# ENV1.net
KiCad netlist of a schematic drawn in EAGLE
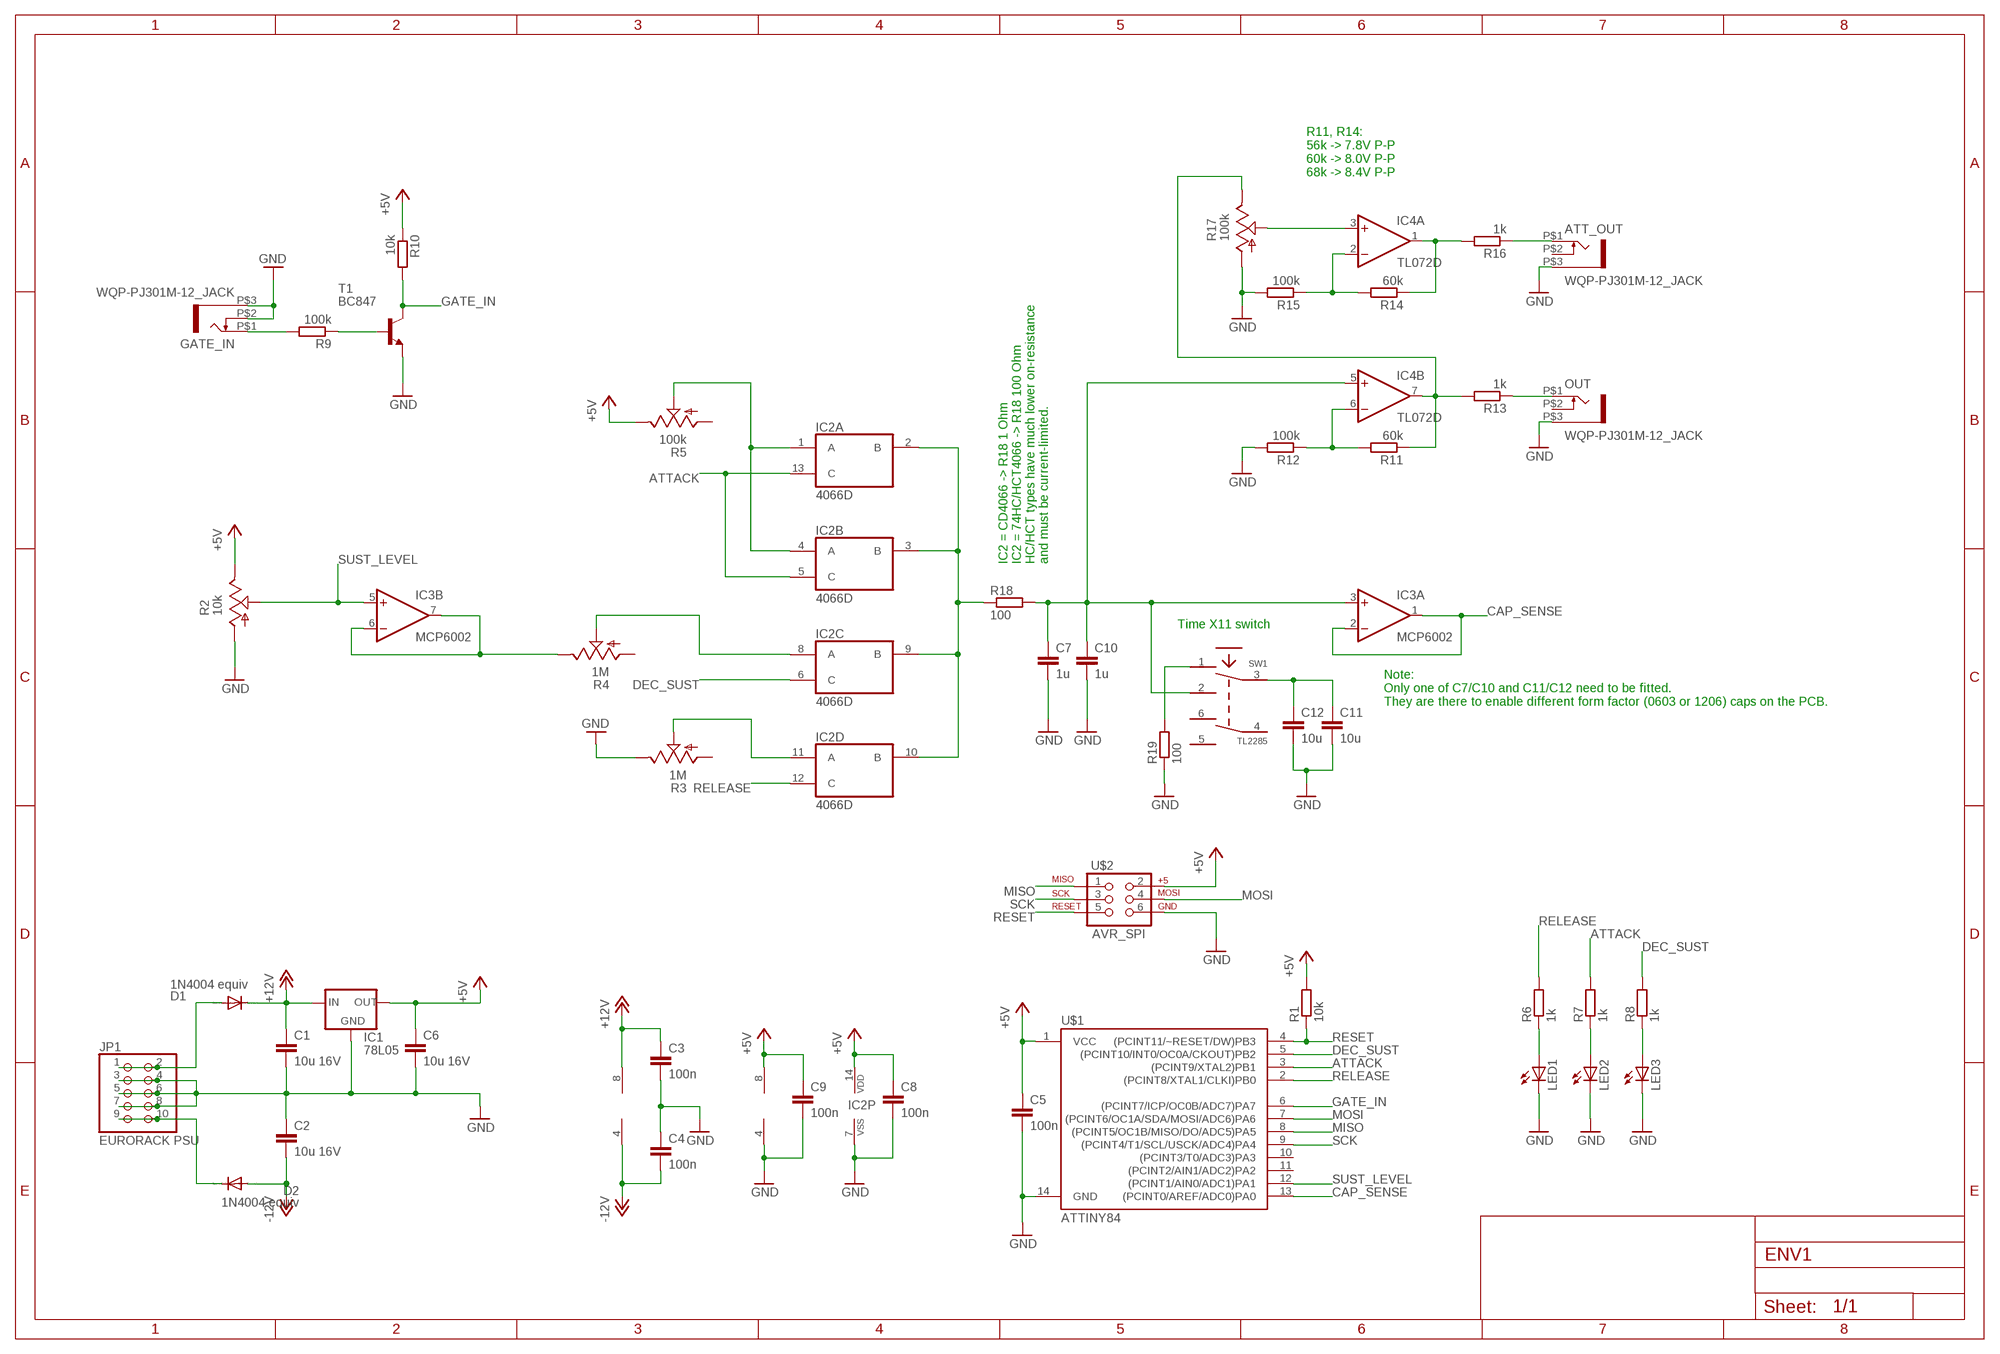
[diagram p0: schematic, sheet 1]

(export (version "E")
  (design (tool "Eeschema 10.0.6"))
  (components
    (comp (ref "ATT_OUT")
      (value "WQP-PJ301M-12_JACK")
      (footprint "eagle-import:WQP-PJ301M-12_JACK")
      (libsource (lib "eagle-import") (part "WQP-PJ301M-12_JACK"))
    )
    (comp (ref "C1")
      (value "10u 16V")
      (footprint "eagle-import:C1206K")
      (libsource (lib "eagle-import") (part "C-EUC1206K"))
    )
    (comp (ref "C2")
      (value "10u 16V")
      (footprint "eagle-import:C1206K")
      (libsource (lib "eagle-import") (part "C-EUC1206K"))
    )
    (comp (ref "C3")
      (value "100n")
      (footprint "eagle-import:C0603K")
      (libsource (lib "eagle-import") (part "C-EUC0603K"))
    )
    (comp (ref "C4")
      (value "100n")
      (footprint "eagle-import:C0603K")
      (libsource (lib "eagle-import") (part "C-EUC0603K"))
    )
    (comp (ref "C5")
      (value "100n")
      (footprint "eagle-import:C0603K")
      (libsource (lib "eagle-import") (part "C-EUC0603K"))
    )
    (comp (ref "C6")
      (value "10u 16V")
      (footprint "eagle-import:C1206K")
      (libsource (lib "eagle-import") (part "C-EUC1206K"))
    )
    (comp (ref "C7")
      (value "1u")
      (footprint "eagle-import:C0603K")
      (libsource (lib "eagle-import") (part "C-EUC0603K"))
    )
    (comp (ref "C8")
      (value "100n")
      (footprint "eagle-import:C0603K")
      (libsource (lib "eagle-import") (part "C-EUC0603K"))
    )
    (comp (ref "C9")
      (value "100n")
      (footprint "eagle-import:C0603K")
      (libsource (lib "eagle-import") (part "C-EUC0603K"))
    )
    (comp (ref "C10")
      (value "1u")
      (footprint "eagle-import:C1206K")
      (libsource (lib "eagle-import") (part "C-EUC1206K"))
    )
    (comp (ref "C11")
      (value "10u")
      (footprint "eagle-import:C1206K")
      (libsource (lib "eagle-import") (part "C-EUC1206K"))
    )
    (comp (ref "C12")
      (value "10u")
      (footprint "eagle-import:C0603K")
      (libsource (lib "eagle-import") (part "C-EUC0603K"))
    )
    (comp (ref "D1")
      (value "1N4004 equiv")
      (footprint "eagle-import:DO214AA")
      (libsource (lib "eagle-import") (part "DIODE-DO214AA"))
    )
    (comp (ref "D2")
      (value "1N4004 equiv")
      (footprint "eagle-import:DO214AA")
      (libsource (lib "eagle-import") (part "DIODE-DO214AA"))
    )
    (comp (ref "GATE_IN")
      (value "WQP-PJ301M-12_JACK")
      (footprint "eagle-import:WQP-PJ301M-12_JACK")
      (libsource (lib "eagle-import") (part "WQP-PJ301M-12_JACK"))
    )
    (comp (ref "IC1")
      (value "78L05")
      (footprint "eagle-import:SOT89R")
      (libsource (lib "eagle-import") (part "78LXXSMD"))
    )
    (comp (ref "IC2")
      (value "4066D")
      (footprint "eagle-import:SO14")
      (libsource (lib "eagle-import") (part "4066D"))
    )
    (comp (ref "IC3")
      (value "MCP6002")
      (footprint "eagle-import:SO08")
      (libsource (lib "eagle-import") (part "TL072D"))
    )
    (comp (ref "IC4")
      (value "TL072D")
      (footprint "eagle-import:SO08")
      (libsource (lib "eagle-import") (part "TL072D"))
    )
    (comp (ref "JP1")
      (value "EURORACK PSU")
      (footprint "eagle-import:2X05")
      (libsource (lib "eagle-import") (part "PINHD-2X5"))
    )
    (comp (ref "LED1")
      (value "LED3MM")
      (footprint "eagle-import:LED3MM")
      (libsource (lib "eagle-import") (part "LED3MM"))
    )
    (comp (ref "LED2")
      (value "LED3MM")
      (footprint "eagle-import:LED3MM")
      (libsource (lib "eagle-import") (part "LED3MM"))
    )
    (comp (ref "LED3")
      (value "LED3MM")
      (footprint "eagle-import:LED3MM")
      (libsource (lib "eagle-import") (part "LED3MM"))
    )
    (comp (ref "OUT")
      (value "WQP-PJ301M-12_JACK")
      (footprint "eagle-import:WQP-PJ301M-12_JACK")
      (libsource (lib "eagle-import") (part "WQP-PJ301M-12_JACK"))
    )
    (comp (ref "R1")
      (value "10k")
      (footprint "eagle-import:R0603")
      (libsource (lib "eagle-import") (part "R-EU_R0603"))
    )
    (comp (ref "R2")
      (value "10k")
      (footprint "eagle-import:ALPS_POT_VERTICAL")
      (libsource (lib "eagle-import") (part "POT_USVERTICAL"))
    )
    (comp (ref "R3")
      (value "1M")
      (footprint "eagle-import:ALPS_POT_VERTICAL")
      (libsource (lib "eagle-import") (part "POT_USVERTICAL"))
    )
    (comp (ref "R4")
      (value "1M")
      (footprint "eagle-import:ALPS_POT_VERTICAL")
      (libsource (lib "eagle-import") (part "POT_USVERTICAL"))
    )
    (comp (ref "R5")
      (value "100k")
      (footprint "eagle-import:ALPS_POT_VERTICAL")
      (libsource (lib "eagle-import") (part "POT_USVERTICAL"))
    )
    (comp (ref "R6")
      (value "1k")
      (footprint "eagle-import:R0603")
      (libsource (lib "eagle-import") (part "R-EU_R0603"))
    )
    (comp (ref "R7")
      (value "1k")
      (footprint "eagle-import:R0603")
      (libsource (lib "eagle-import") (part "R-EU_R0603"))
    )
    (comp (ref "R8")
      (value "1k")
      (footprint "eagle-import:R0603")
      (libsource (lib "eagle-import") (part "R-EU_R0603"))
    )
    (comp (ref "R9")
      (value "100k")
      (footprint "eagle-import:R0603")
      (libsource (lib "eagle-import") (part "R-EU_R0603"))
    )
    (comp (ref "R10")
      (value "10k")
      (footprint "eagle-import:R0603")
      (libsource (lib "eagle-import") (part "R-EU_R0603"))
    )
    (comp (ref "R11")
      (value "60k")
      (footprint "eagle-import:R0603")
      (libsource (lib "eagle-import") (part "R-EU_R0603"))
    )
    (comp (ref "R12")
      (value "100k")
      (footprint "eagle-import:R0603")
      (libsource (lib "eagle-import") (part "R-EU_R0603"))
    )
    (comp (ref "R13")
      (value "1k")
      (footprint "eagle-import:R0603")
      (libsource (lib "eagle-import") (part "R-EU_R0603"))
    )
    (comp (ref "R14")
      (value "60k")
      (footprint "eagle-import:R0603")
      (libsource (lib "eagle-import") (part "R-EU_R0603"))
    )
    (comp (ref "R15")
      (value "100k")
      (footprint "eagle-import:R0603")
      (libsource (lib "eagle-import") (part "R-EU_R0603"))
    )
    (comp (ref "R16")
      (value "1k")
      (footprint "eagle-import:R0603")
      (libsource (lib "eagle-import") (part "R-EU_R0603"))
    )
    (comp (ref "R17")
      (value "100k")
      (footprint "eagle-import:ALPS_POT_VERTICAL")
      (libsource (lib "eagle-import") (part "POT_USVERTICAL"))
    )
    (comp (ref "R18")
      (value "100")
      (footprint "eagle-import:R1206")
      (libsource (lib "eagle-import") (part "R-EU_R1206"))
    )
    (comp (ref "R19")
      (value "100")
      (footprint "eagle-import:R1206")
      (libsource (lib "eagle-import") (part "R-EU_R1206"))
    )
    (comp (ref "SW1")
      (value "TL2285")
      (footprint "eagle-import:TL2285_PCB")
      (libsource (lib "eagle-import") (part "TL2285"))
    )
    (comp (ref "T1")
      (value "BC847")
      (footprint "eagle-import:SOT23")
      (libsource (lib "eagle-import") (part "BC847"))
    )
    (comp (ref "U$1")
      (value "ATTINY84")
      (footprint "eagle-import:SO14")
      (libsource (lib "eagle-import") (part "ATTINY84"))
    )
    (comp (ref "U$2")
      (value "AVR_SPI")
      (footprint "eagle-import:2X3")
      (libsource (lib "eagle-import") (part "AVR_SPI_PRG_6PTH"))
    )
  )
  (nets
    (net (code "1") (name "+5V") (class "Default")
      (node (ref "C5") (pin "1") (pinfunction "1_1") (pintype "passive"))
      (node (ref "C6") (pin "1") (pinfunction "1_1") (pintype "passive"))
      (node (ref "C8") (pin "1") (pinfunction "1_1") (pintype "passive"))
      (node (ref "C9") (pin "1") (pinfunction "1_1") (pintype "passive"))
      (node (ref "IC1") (pin "PAD1") (pinfunction "OUT_PAD1") (pintype "passive"))
      (node (ref "IC2") (pin "14") (pinfunction "VDD_14") (pintype "power_in"))
      (node (ref "IC3") (pin "8") (pinfunction "V+_8") (pintype "power_in"))
      (node (ref "R1") (pin "2") (pinfunction "2_2") (pintype "passive"))
      (node (ref "R10") (pin "1") (pinfunction "1_1") (pintype "passive"))
      (node (ref "R2") (pin "P$1") (pinfunction "E_P$1") (pintype "passive"))
      (node (ref "R5") (pin "P$1") (pinfunction "E_P$1") (pintype "passive"))
      (node (ref "U$1") (pin "1") (pinfunction "VCC_1") (pintype "bidirectional"))
      (node (ref "U$2") (pin "2") (pinfunction "2_2") (pintype "passive"))
    )
    (net (code "2") (name "+12V") (class "Default")
      (node (ref "C1") (pin "1") (pinfunction "1_1") (pintype "passive"))
      (node (ref "C3") (pin "1") (pinfunction "1_1") (pintype "passive"))
      (node (ref "D1") (pin "C") (pinfunction "C_C") (pintype "passive"))
      (node (ref "IC1") (pin "PAD3") (pinfunction "IN_PAD3") (pintype "input"))
      (node (ref "IC4") (pin "8") (pinfunction "V+_8") (pintype "power_in"))
    )
    (net (code "3") (name "-12V") (class "Default")
      (node (ref "C2") (pin "2") (pinfunction "2_2") (pintype "passive"))
      (node (ref "C4") (pin "2") (pinfunction "2_2") (pintype "passive"))
      (node (ref "D2") (pin "A") (pinfunction "A_A") (pintype "passive"))
      (node (ref "IC4") (pin "4") (pinfunction "V-_4") (pintype "power_in"))
    )
    (net (code "4") (name "/ATTACK") (class "Default")
      (node (ref "IC2") (pin "13") (pinfunction "C_13") (pintype "input"))
      (node (ref "IC2") (pin "5") (pinfunction "C_5") (pintype "input"))
      (node (ref "R7") (pin "2") (pinfunction "2_2") (pintype "passive"))
      (node (ref "U$1") (pin "3") (pinfunction "(PCINT9/XTAL2)PB1_3") (pintype "bidirectional"))
    )
    (net (code "5") (name "/CAP_SENSE") (class "Default")
      (node (ref "IC3") (pin "1") (pinfunction "OUT_1") (pintype "output"))
      (node (ref "IC3") (pin "2") (pinfunction "-IN_2") (pintype "input"))
      (node (ref "U$1") (pin "13") (pinfunction "(PCINT0/AREF/ADC0)PA0_13") (pintype "bidirectional"))
    )
    (net (code "6") (name "/DEC_SUST") (class "Default")
      (node (ref "IC2") (pin "6") (pinfunction "C_6") (pintype "input"))
      (node (ref "R8") (pin "2") (pinfunction "2_2") (pintype "passive"))
      (node (ref "U$1") (pin "5") (pinfunction "(PCINT10/INT0/OC0A/CKOUT)PB2_5") (pintype "bidirectional"))
    )
    (net (code "7") (name "/GATE_IN") (class "Default")
      (node (ref "R10") (pin "2") (pinfunction "2_2") (pintype "passive"))
      (node (ref "T1") (pin "3") (pinfunction "C_3") (pintype "passive"))
      (node (ref "U$1") (pin "6") (pinfunction "(PCINT7/ICP/OC0B/ADC7)PA7_6") (pintype "bidirectional"))
    )
    (net (code "8") (name "/MISO") (class "Default")
      (node (ref "U$1") (pin "8") (pinfunction "(PCINT5/OC1B/MISO/DO/ADC5)PA5_8") (pintype "bidirectional"))
      (node (ref "U$2") (pin "1") (pinfunction "1_1") (pintype "passive"))
    )
    (net (code "9") (name "/MOSI") (class "Default")
      (node (ref "U$1") (pin "7") (pinfunction "(PCINT6/OC1A/SDA/MOSI/ADC6)PA6_7") (pintype "bidirectional"))
      (node (ref "U$2") (pin "4") (pinfunction "4_4") (pintype "passive"))
    )
    (net (code "10") (name "/RELEASE") (class "Default")
      (node (ref "IC2") (pin "12") (pinfunction "C_12") (pintype "input"))
      (node (ref "R6") (pin "2") (pinfunction "2_2") (pintype "passive"))
      (node (ref "U$1") (pin "2") (pinfunction "(PCINT8/XTAL1/CLKI)PB0_2") (pintype "bidirectional"))
    )
    (net (code "11") (name "/RESET") (class "Default")
      (node (ref "R1") (pin "1") (pinfunction "1_1") (pintype "passive"))
      (node (ref "U$1") (pin "4") (pinfunction "(PCINT11/~{RESET/DW})PB3_4") (pintype "bidirectional"))
      (node (ref "U$2") (pin "5") (pinfunction "5_5") (pintype "passive"))
    )
    (net (code "12") (name "/SCK") (class "Default")
      (node (ref "U$1") (pin "9") (pinfunction "(PCINT4/T1/SCL/USCK/ADC4)PA4_9") (pintype "bidirectional"))
      (node (ref "U$2") (pin "3") (pinfunction "3_3") (pintype "passive"))
    )
    (net (code "13") (name "/SUST_LEVEL") (class "Default")
      (node (ref "IC3") (pin "5") (pinfunction "+IN_5") (pintype "input"))
      (node (ref "R2") (pin "P$2") (pinfunction "S_P$2") (pintype "passive"))
      (node (ref "U$1") (pin "12") (pinfunction "(PCINT1/AIN0/ADC1)PA1_12") (pintype "bidirectional"))
    )
    (net (code "14") (name "GND") (class "Default")
      (node (ref "ATT_OUT") (pin "P$3") (pinfunction "1_P$3") (pintype "passive"))
      (node (ref "C1") (pin "2") (pinfunction "2_2") (pintype "passive"))
      (node (ref "C10") (pin "2") (pinfunction "2_2") (pintype "passive"))
      (node (ref "C11") (pin "2") (pinfunction "2_2") (pintype "passive"))
      (node (ref "C12") (pin "2") (pinfunction "2_2") (pintype "passive"))
      (node (ref "C2") (pin "1") (pinfunction "1_1") (pintype "passive"))
      (node (ref "C3") (pin "2") (pinfunction "2_2") (pintype "passive"))
      (node (ref "C4") (pin "1") (pinfunction "1_1") (pintype "passive"))
      (node (ref "C5") (pin "2") (pinfunction "2_2") (pintype "passive"))
      (node (ref "C6") (pin "2") (pinfunction "2_2") (pintype "passive"))
      (node (ref "C7") (pin "2") (pinfunction "2_2") (pintype "passive"))
      (node (ref "C8") (pin "2") (pinfunction "2_2") (pintype "passive"))
      (node (ref "C9") (pin "2") (pinfunction "2_2") (pintype "passive"))
      (node (ref "GATE_IN") (pin "P$2") (pinfunction "3_P$2") (pintype "passive"))
      (node (ref "GATE_IN") (pin "P$3") (pinfunction "1_P$3") (pintype "passive"))
      (node (ref "IC1") (pin "PAD2") (pinfunction "GND_PAD2") (pintype "input"))
      (node (ref "IC1") (pin "PAD4") (pinfunction "GND_PAD4") (pintype "input"))
      (node (ref "IC2") (pin "7") (pinfunction "VSS_7") (pintype "power_in"))
      (node (ref "IC3") (pin "4") (pinfunction "V-_4") (pintype "power_in"))
      (node (ref "JP1") (pin "3") (pinfunction "3_3") (pintype "passive"))
      (node (ref "JP1") (pin "4") (pinfunction "4_4") (pintype "passive"))
      (node (ref "JP1") (pin "5") (pinfunction "5_5") (pintype "passive"))
      (node (ref "JP1") (pin "6") (pinfunction "6_6") (pintype "passive"))
      (node (ref "JP1") (pin "7") (pinfunction "7_7") (pintype "passive"))
      (node (ref "JP1") (pin "8") (pinfunction "8_8") (pintype "passive"))
      (node (ref "LED1") (pin "K") (pinfunction "C_K") (pintype "passive"))
      (node (ref "LED2") (pin "K") (pinfunction "C_K") (pintype "passive"))
      (node (ref "LED3") (pin "K") (pinfunction "C_K") (pintype "passive"))
      (node (ref "OUT") (pin "P$3") (pinfunction "1_P$3") (pintype "passive"))
      (node (ref "R12") (pin "2") (pinfunction "2_2") (pintype "passive"))
      (node (ref "R15") (pin "2") (pinfunction "2_2") (pintype "passive"))
      (node (ref "R17") (pin "P$3") (pinfunction "A_P$3") (pintype "passive"))
      (node (ref "R19") (pin "1") (pinfunction "1_1") (pintype "passive"))
      (node (ref "R2") (pin "P$3") (pinfunction "A_P$3") (pintype "passive"))
      (node (ref "R3") (pin "P$1") (pinfunction "E_P$1") (pintype "passive"))
      (node (ref "T1") (pin "2") (pinfunction "E_2") (pintype "passive"))
      (node (ref "U$1") (pin "14") (pinfunction "GND_14") (pintype "bidirectional"))
      (node (ref "U$2") (pin "6") (pinfunction "6_6") (pintype "passive"))
    )
    (net (code "15") (name "Net-(ATT_OUT-2)") (class "Default")
      (node (ref "ATT_OUT") (pin "P$1") (pinfunction "2_P$1") (pintype "passive"))
      (node (ref "R16") (pin "1") (pinfunction "1_1") (pintype "passive"))
    )
    (net (code "16") (name "Net-(D1-PadA)") (class "Default")
      (node (ref "D1") (pin "A") (pinfunction "A_A") (pintype "passive"))
      (node (ref "JP1") (pin "1") (pinfunction "1_1") (pintype "passive"))
      (node (ref "JP1") (pin "2") (pinfunction "2_2") (pintype "passive"))
    )
    (net (code "17") (name "Net-(D2-PadC)") (class "Default")
      (node (ref "D2") (pin "C") (pinfunction "C_C") (pintype "passive"))
      (node (ref "JP1") (pin "10") (pinfunction "10_10") (pintype "passive"))
      (node (ref "JP1") (pin "9") (pinfunction "9_9") (pintype "passive"))
    )
    (net (code "18") (name "Net-(GATE_IN-2)") (class "Default")
      (node (ref "GATE_IN") (pin "P$1") (pinfunction "2_P$1") (pintype "passive"))
      (node (ref "R9") (pin "2") (pinfunction "2_2") (pintype "passive"))
    )
    (net (code "19") (name "Net-(IC2A-A)") (class "Default")
      (node (ref "IC2") (pin "1") (pinfunction "A_1") (pintype "tri_state"))
      (node (ref "IC2") (pin "4") (pinfunction "A_4") (pintype "tri_state"))
      (node (ref "R5") (pin "P$2") (pinfunction "S_P$2") (pintype "passive"))
    )
    (net (code "20") (name "Net-(IC2A-B)") (class "Default")
      (node (ref "IC2") (pin "10") (pinfunction "B_10") (pintype "tri_state"))
      (node (ref "IC2") (pin "2") (pinfunction "B_2") (pintype "tri_state"))
      (node (ref "IC2") (pin "3") (pinfunction "B_3") (pintype "tri_state"))
      (node (ref "IC2") (pin "9") (pinfunction "B_9") (pintype "tri_state"))
      (node (ref "R18") (pin "1") (pinfunction "1_1") (pintype "passive"))
    )
    (net (code "21") (name "Net-(IC2C-A)") (class "Default")
      (node (ref "IC2") (pin "8") (pinfunction "A_8") (pintype "tri_state"))
      (node (ref "R4") (pin "P$2") (pinfunction "S_P$2") (pintype "passive"))
    )
    (net (code "22") (name "Net-(IC2D-A)") (class "Default")
      (node (ref "IC2") (pin "11") (pinfunction "A_11") (pintype "tri_state"))
      (node (ref "R3") (pin "P$2") (pinfunction "S_P$2") (pintype "passive"))
    )
    (net (code "23") (name "Net-(IC3A-+IN)") (class "Default")
      (node (ref "C10") (pin "1") (pinfunction "1_1") (pintype "passive"))
      (node (ref "C7") (pin "1") (pinfunction "1_1") (pintype "passive"))
      (node (ref "IC3") (pin "3") (pinfunction "+IN_3") (pintype "input"))
      (node (ref "IC4") (pin "5") (pinfunction "+IN_5") (pintype "input"))
      (node (ref "R18") (pin "2") (pinfunction "2_2") (pintype "passive"))
      (node (ref "SW1") (pin "2") (pinfunction "P2_2") (pintype "bidirectional"))
    )
    (net (code "24") (name "Net-(IC3B--IN)") (class "Default")
      (node (ref "IC3") (pin "6") (pinfunction "-IN_6") (pintype "input"))
      (node (ref "IC3") (pin "7") (pinfunction "OUT_7") (pintype "output"))
      (node (ref "R4") (pin "P$1") (pinfunction "E_P$1") (pintype "passive"))
    )
    (net (code "25") (name "Net-(IC4A-+IN)") (class "Default")
      (node (ref "IC4") (pin "3") (pinfunction "+IN_3") (pintype "input"))
      (node (ref "R17") (pin "P$2") (pinfunction "S_P$2") (pintype "passive"))
    )
    (net (code "26") (name "Net-(IC4A--IN)") (class "Default")
      (node (ref "IC4") (pin "2") (pinfunction "-IN_2") (pintype "input"))
      (node (ref "R14") (pin "2") (pinfunction "2_2") (pintype "passive"))
      (node (ref "R15") (pin "1") (pinfunction "1_1") (pintype "passive"))
    )
    (net (code "27") (name "Net-(IC4A-OUT)") (class "Default")
      (node (ref "IC4") (pin "1") (pinfunction "OUT_1") (pintype "output"))
      (node (ref "R14") (pin "1") (pinfunction "1_1") (pintype "passive"))
      (node (ref "R16") (pin "2") (pinfunction "2_2") (pintype "passive"))
    )
    (net (code "28") (name "Net-(IC4B--IN)") (class "Default")
      (node (ref "IC4") (pin "6") (pinfunction "-IN_6") (pintype "input"))
      (node (ref "R11") (pin "2") (pinfunction "2_2") (pintype "passive"))
      (node (ref "R12") (pin "1") (pinfunction "1_1") (pintype "passive"))
    )
    (net (code "29") (name "Net-(IC4B-OUT)") (class "Default")
      (node (ref "IC4") (pin "7") (pinfunction "OUT_7") (pintype "output"))
      (node (ref "R11") (pin "1") (pinfunction "1_1") (pintype "passive"))
      (node (ref "R13") (pin "2") (pinfunction "2_2") (pintype "passive"))
      (node (ref "R17") (pin "P$1") (pinfunction "E_P$1") (pintype "passive"))
    )
    (net (code "30") (name "Net-(LED1-PadA)") (class "Default")
      (node (ref "LED1") (pin "A") (pinfunction "A_A") (pintype "passive"))
      (node (ref "R6") (pin "1") (pinfunction "1_1") (pintype "passive"))
    )
    (net (code "31") (name "Net-(LED2-PadA)") (class "Default")
      (node (ref "LED2") (pin "A") (pinfunction "A_A") (pintype "passive"))
      (node (ref "R7") (pin "1") (pinfunction "1_1") (pintype "passive"))
    )
    (net (code "32") (name "Net-(LED3-PadA)") (class "Default")
      (node (ref "LED3") (pin "A") (pinfunction "A_A") (pintype "passive"))
      (node (ref "R8") (pin "1") (pinfunction "1_1") (pintype "passive"))
    )
    (net (code "33") (name "Net-(OUT-2)") (class "Default")
      (node (ref "OUT") (pin "P$1") (pinfunction "2_P$1") (pintype "passive"))
      (node (ref "R13") (pin "1") (pinfunction "1_1") (pintype "passive"))
    )
    (net (code "34") (name "Net-(SW1-P1)") (class "Default")
      (node (ref "R19") (pin "2") (pinfunction "2_2") (pintype "passive"))
      (node (ref "SW1") (pin "1") (pinfunction "P1_1") (pintype "bidirectional"))
    )
    (net (code "35") (name "Net-(SW1-P3)") (class "Default")
      (node (ref "C11") (pin "1") (pinfunction "1_1") (pintype "passive"))
      (node (ref "C12") (pin "1") (pinfunction "1_1") (pintype "passive"))
      (node (ref "SW1") (pin "3") (pinfunction "P3_3") (pintype "bidirectional"))
    )
    (net (code "36") (name "Net-(T1-B)") (class "Default")
      (node (ref "R9") (pin "1") (pinfunction "1_1") (pintype "passive"))
      (node (ref "T1") (pin "1") (pinfunction "B_1") (pintype "passive"))
    )
    (net (code "37") (name "unconnected-(ATT_OUT-3-PadP$2)") (class "Default")
      (node (ref "ATT_OUT") (pin "P$2") (pinfunction "3_P$2") (pintype "passive"))
    )
    (net (code "38") (name "unconnected-(OUT-3-PadP$2)") (class "Default")
      (node (ref "OUT") (pin "P$2") (pinfunction "3_P$2") (pintype "passive"))
    )
    (net (code "39") (name "unconnected-(R3-A-PadP$3)") (class "Default")
      (node (ref "R3") (pin "P$3") (pinfunction "A_P$3") (pintype "passive"))
    )
    (net (code "40") (name "unconnected-(R4-A-PadP$3)") (class "Default")
      (node (ref "R4") (pin "P$3") (pinfunction "A_P$3") (pintype "passive"))
    )
    (net (code "41") (name "unconnected-(R5-A-PadP$3)") (class "Default")
      (node (ref "R5") (pin "P$3") (pinfunction "A_P$3") (pintype "passive"))
    )
    (net (code "42") (name "unconnected-(SW1-P4-Pad4)") (class "Default")
      (node (ref "SW1") (pin "4") (pinfunction "P4_4") (pintype "bidirectional"))
    )
    (net (code "43") (name "unconnected-(SW1-P5-Pad5)") (class "Default")
      (node (ref "SW1") (pin "5") (pinfunction "P5_5") (pintype "bidirectional"))
    )
    (net (code "44") (name "unconnected-(SW1-P6-Pad6)") (class "Default")
      (node (ref "SW1") (pin "6") (pinfunction "P6_6") (pintype "bidirectional"))
    )
    (net (code "45") (name "unconnected-(U$1-(PCINT2{slash}AIN1{slash}ADC2)PA2-Pad11)") (class "Default")
      (node (ref "U$1") (pin "11") (pinfunction "(PCINT2/AIN1/ADC2)PA2_11") (pintype "bidirectional"))
    )
    (net (code "46") (name "unconnected-(U$1-(PCINT3{slash}T0{slash}ADC3)PA3-Pad10)") (class "Default")
      (node (ref "U$1") (pin "10") (pinfunction "(PCINT3/T0/ADC3)PA3_10") (pintype "bidirectional"))
    )
  )
)
